# main_controler.net
KiCad netlist of a schematic drawn in EAGLE
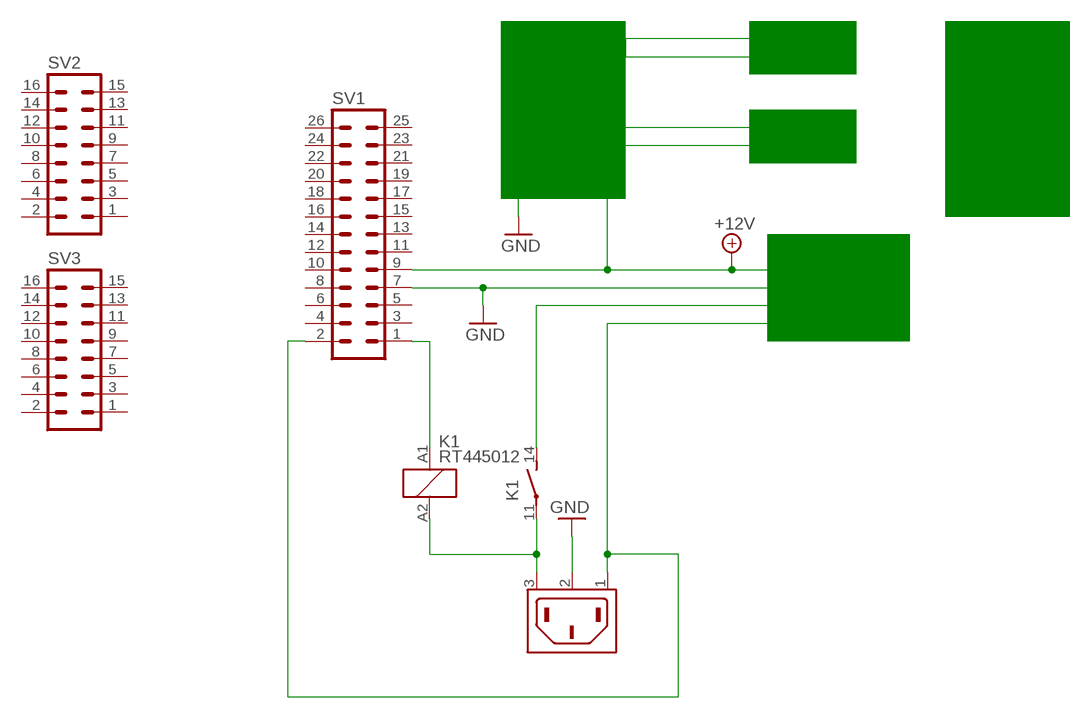
[diagram p0: schematic, sheet 1]

(export (version "E")
  (design (tool "Eeschema 10.0.6"))
  (components
    (comp (ref "K1")
      (value "RT445012")
      (footprint "eagle-import:RT2N_O")
      (libsource (lib "eagle-import") (part "RT44?5012"))
    )
    (comp (ref "SV1")
      (value "MA13-2")
      (footprint "eagle-import:MA13-2")
      (libsource (lib "eagle-import") (part "MA13-2"))
    )
    (comp (ref "SV2")
      (value "MA08-2")
      (footprint "eagle-import:MA08-2")
      (libsource (lib "eagle-import") (part "MA08-2"))
    )
    (comp (ref "SV3")
      (value "MA08-2")
      (footprint "eagle-import:MA08-2")
      (libsource (lib "eagle-import") (part "MA08-2"))
    )
    (comp (ref "X1")
      (value "6ESRM-P")
      (footprint "eagle-import:6ESRM-P")
      (fields (field (name "MF") "TYCO ELECTRONICS"))
      (libsource (lib "eagle-import") (part "6ESRM-P"))
    )
  )
  (nets
    (net (code "1") (name "+12V") (class "Default")
      (node (ref "SV1") (pin "9") (pinfunction "9_9") (pintype "passive"))
    )
    (net (code "2") (name "GND") (class "Default")
      (node (ref "SV1") (pin "7") (pinfunction "7_7") (pintype "passive"))
      (node (ref "X1") (pin "2") (pinfunction "SH_2") (pintype "passive"))
    )
    (net (code "3") (name "Net-(K1A-1)") (class "Default")
      (node (ref "K1") (pin "A1") (pinfunction "1_A1") (pintype "passive"))
      (node (ref "SV1") (pin "1") (pinfunction "1_1") (pintype "passive"))
    )
    (net (code "4") (name "Net-(K1A-2)") (class "Default")
      (node (ref "K1") (pin "11") (pinfunction "P_11") (pintype "passive"))
      (node (ref "K1") (pin "A2") (pinfunction "2_A2") (pintype "passive"))
      (node (ref "X1") (pin "3") (pinfunction "AC2_3") (pintype "passive"))
    )
    (net (code "5") (name "Net-(X1-AC1)") (class "Default")
      (node (ref "SV1") (pin "2") (pinfunction "2_2") (pintype "passive"))
      (node (ref "X1") (pin "1") (pinfunction "AC1_1") (pintype "passive"))
    )
    (net (code "6") (name "unconnected-(K1B-S-Pad14)") (class "Default")
      (node (ref "K1") (pin "14") (pinfunction "S_14") (pintype "passive"))
    )
    (net (code "7") (name "unconnected-(SV1-Pad3)") (class "Default")
      (node (ref "SV1") (pin "3") (pinfunction "3_3") (pintype "passive"))
    )
    (net (code "8") (name "unconnected-(SV1-Pad4)") (class "Default")
      (node (ref "SV1") (pin "4") (pinfunction "4_4") (pintype "passive"))
    )
    (net (code "9") (name "unconnected-(SV1-Pad5)") (class "Default")
      (node (ref "SV1") (pin "5") (pinfunction "5_5") (pintype "passive"))
    )
    (net (code "10") (name "unconnected-(SV1-Pad6)") (class "Default")
      (node (ref "SV1") (pin "6") (pinfunction "6_6") (pintype "passive"))
    )
    (net (code "11") (name "unconnected-(SV1-Pad8)") (class "Default")
      (node (ref "SV1") (pin "8") (pinfunction "8_8") (pintype "passive"))
    )
    (net (code "12") (name "unconnected-(SV1-Pad10)") (class "Default")
      (node (ref "SV1") (pin "10") (pinfunction "10_10") (pintype "passive"))
    )
    (net (code "13") (name "unconnected-(SV1-Pad11)") (class "Default")
      (node (ref "SV1") (pin "11") (pinfunction "11_11") (pintype "passive"))
    )
    (net (code "14") (name "unconnected-(SV1-Pad12)") (class "Default")
      (node (ref "SV1") (pin "12") (pinfunction "12_12") (pintype "passive"))
    )
    (net (code "15") (name "unconnected-(SV1-Pad13)") (class "Default")
      (node (ref "SV1") (pin "13") (pinfunction "13_13") (pintype "passive"))
    )
    (net (code "16") (name "unconnected-(SV1-Pad14)") (class "Default")
      (node (ref "SV1") (pin "14") (pinfunction "14_14") (pintype "passive"))
    )
    (net (code "17") (name "unconnected-(SV1-Pad15)") (class "Default")
      (node (ref "SV1") (pin "15") (pinfunction "15_15") (pintype "passive"))
    )
    (net (code "18") (name "unconnected-(SV1-Pad16)") (class "Default")
      (node (ref "SV1") (pin "16") (pinfunction "16_16") (pintype "passive"))
    )
    (net (code "19") (name "unconnected-(SV1-Pad17)") (class "Default")
      (node (ref "SV1") (pin "17") (pinfunction "17_17") (pintype "passive"))
    )
    (net (code "20") (name "unconnected-(SV1-Pad18)") (class "Default")
      (node (ref "SV1") (pin "18") (pinfunction "18_18") (pintype "passive"))
    )
    (net (code "21") (name "unconnected-(SV1-Pad19)") (class "Default")
      (node (ref "SV1") (pin "19") (pinfunction "19_19") (pintype "passive"))
    )
    (net (code "22") (name "unconnected-(SV1-Pad20)") (class "Default")
      (node (ref "SV1") (pin "20") (pinfunction "20_20") (pintype "passive"))
    )
    (net (code "23") (name "unconnected-(SV1-Pad21)") (class "Default")
      (node (ref "SV1") (pin "21") (pinfunction "21_21") (pintype "passive"))
    )
    (net (code "24") (name "unconnected-(SV1-Pad22)") (class "Default")
      (node (ref "SV1") (pin "22") (pinfunction "22_22") (pintype "passive"))
    )
    (net (code "25") (name "unconnected-(SV1-Pad23)") (class "Default")
      (node (ref "SV1") (pin "23") (pinfunction "23_23") (pintype "passive"))
    )
    (net (code "26") (name "unconnected-(SV1-Pad24)") (class "Default")
      (node (ref "SV1") (pin "24") (pinfunction "24_24") (pintype "passive"))
    )
    (net (code "27") (name "unconnected-(SV1-Pad25)") (class "Default")
      (node (ref "SV1") (pin "25") (pinfunction "25_25") (pintype "passive"))
    )
    (net (code "28") (name "unconnected-(SV1-Pad26)") (class "Default")
      (node (ref "SV1") (pin "26") (pinfunction "26_26") (pintype "passive"))
    )
    (net (code "29") (name "unconnected-(SV2-Pad1)") (class "Default")
      (node (ref "SV2") (pin "1") (pinfunction "1_1") (pintype "passive"))
    )
    (net (code "30") (name "unconnected-(SV2-Pad2)") (class "Default")
      (node (ref "SV2") (pin "2") (pinfunction "2_2") (pintype "passive"))
    )
    (net (code "31") (name "unconnected-(SV2-Pad3)") (class "Default")
      (node (ref "SV2") (pin "3") (pinfunction "3_3") (pintype "passive"))
    )
    (net (code "32") (name "unconnected-(SV2-Pad4)") (class "Default")
      (node (ref "SV2") (pin "4") (pinfunction "4_4") (pintype "passive"))
    )
    (net (code "33") (name "unconnected-(SV2-Pad5)") (class "Default")
      (node (ref "SV2") (pin "5") (pinfunction "5_5") (pintype "passive"))
    )
    (net (code "34") (name "unconnected-(SV2-Pad6)") (class "Default")
      (node (ref "SV2") (pin "6") (pinfunction "6_6") (pintype "passive"))
    )
    (net (code "35") (name "unconnected-(SV2-Pad7)") (class "Default")
      (node (ref "SV2") (pin "7") (pinfunction "7_7") (pintype "passive"))
    )
    (net (code "36") (name "unconnected-(SV2-Pad8)") (class "Default")
      (node (ref "SV2") (pin "8") (pinfunction "8_8") (pintype "passive"))
    )
    (net (code "37") (name "unconnected-(SV2-Pad9)") (class "Default")
      (node (ref "SV2") (pin "9") (pinfunction "9_9") (pintype "passive"))
    )
    (net (code "38") (name "unconnected-(SV2-Pad10)") (class "Default")
      (node (ref "SV2") (pin "10") (pinfunction "10_10") (pintype "passive"))
    )
    (net (code "39") (name "unconnected-(SV2-Pad11)") (class "Default")
      (node (ref "SV2") (pin "11") (pinfunction "11_11") (pintype "passive"))
    )
    (net (code "40") (name "unconnected-(SV2-Pad12)") (class "Default")
      (node (ref "SV2") (pin "12") (pinfunction "12_12") (pintype "passive"))
    )
    (net (code "41") (name "unconnected-(SV2-Pad13)") (class "Default")
      (node (ref "SV2") (pin "13") (pinfunction "13_13") (pintype "passive"))
    )
    (net (code "42") (name "unconnected-(SV2-Pad14)") (class "Default")
      (node (ref "SV2") (pin "14") (pinfunction "14_14") (pintype "passive"))
    )
    (net (code "43") (name "unconnected-(SV2-Pad15)") (class "Default")
      (node (ref "SV2") (pin "15") (pinfunction "15_15") (pintype "passive"))
    )
    (net (code "44") (name "unconnected-(SV2-Pad16)") (class "Default")
      (node (ref "SV2") (pin "16") (pinfunction "16_16") (pintype "passive"))
    )
    (net (code "45") (name "unconnected-(SV3-Pad1)") (class "Default")
      (node (ref "SV3") (pin "1") (pinfunction "1_1") (pintype "passive"))
    )
    (net (code "46") (name "unconnected-(SV3-Pad2)") (class "Default")
      (node (ref "SV3") (pin "2") (pinfunction "2_2") (pintype "passive"))
    )
    (net (code "47") (name "unconnected-(SV3-Pad3)") (class "Default")
      (node (ref "SV3") (pin "3") (pinfunction "3_3") (pintype "passive"))
    )
    (net (code "48") (name "unconnected-(SV3-Pad4)") (class "Default")
      (node (ref "SV3") (pin "4") (pinfunction "4_4") (pintype "passive"))
    )
    (net (code "49") (name "unconnected-(SV3-Pad5)") (class "Default")
      (node (ref "SV3") (pin "5") (pinfunction "5_5") (pintype "passive"))
    )
    (net (code "50") (name "unconnected-(SV3-Pad6)") (class "Default")
      (node (ref "SV3") (pin "6") (pinfunction "6_6") (pintype "passive"))
    )
    (net (code "51") (name "unconnected-(SV3-Pad7)") (class "Default")
      (node (ref "SV3") (pin "7") (pinfunction "7_7") (pintype "passive"))
    )
    (net (code "52") (name "unconnected-(SV3-Pad8)") (class "Default")
      (node (ref "SV3") (pin "8") (pinfunction "8_8") (pintype "passive"))
    )
    (net (code "53") (name "unconnected-(SV3-Pad9)") (class "Default")
      (node (ref "SV3") (pin "9") (pinfunction "9_9") (pintype "passive"))
    )
    (net (code "54") (name "unconnected-(SV3-Pad10)") (class "Default")
      (node (ref "SV3") (pin "10") (pinfunction "10_10") (pintype "passive"))
    )
    (net (code "55") (name "unconnected-(SV3-Pad11)") (class "Default")
      (node (ref "SV3") (pin "11") (pinfunction "11_11") (pintype "passive"))
    )
    (net (code "56") (name "unconnected-(SV3-Pad12)") (class "Default")
      (node (ref "SV3") (pin "12") (pinfunction "12_12") (pintype "passive"))
    )
    (net (code "57") (name "unconnected-(SV3-Pad13)") (class "Default")
      (node (ref "SV3") (pin "13") (pinfunction "13_13") (pintype "passive"))
    )
    (net (code "58") (name "unconnected-(SV3-Pad14)") (class "Default")
      (node (ref "SV3") (pin "14") (pinfunction "14_14") (pintype "passive"))
    )
    (net (code "59") (name "unconnected-(SV3-Pad15)") (class "Default")
      (node (ref "SV3") (pin "15") (pinfunction "15_15") (pintype "passive"))
    )
    (net (code "60") (name "unconnected-(SV3-Pad16)") (class "Default")
      (node (ref "SV3") (pin "16") (pinfunction "16_16") (pintype "passive"))
    )
  )
)
